# Uni-2_32.net
KiCad netlist of a schematic drawn in EAGLE
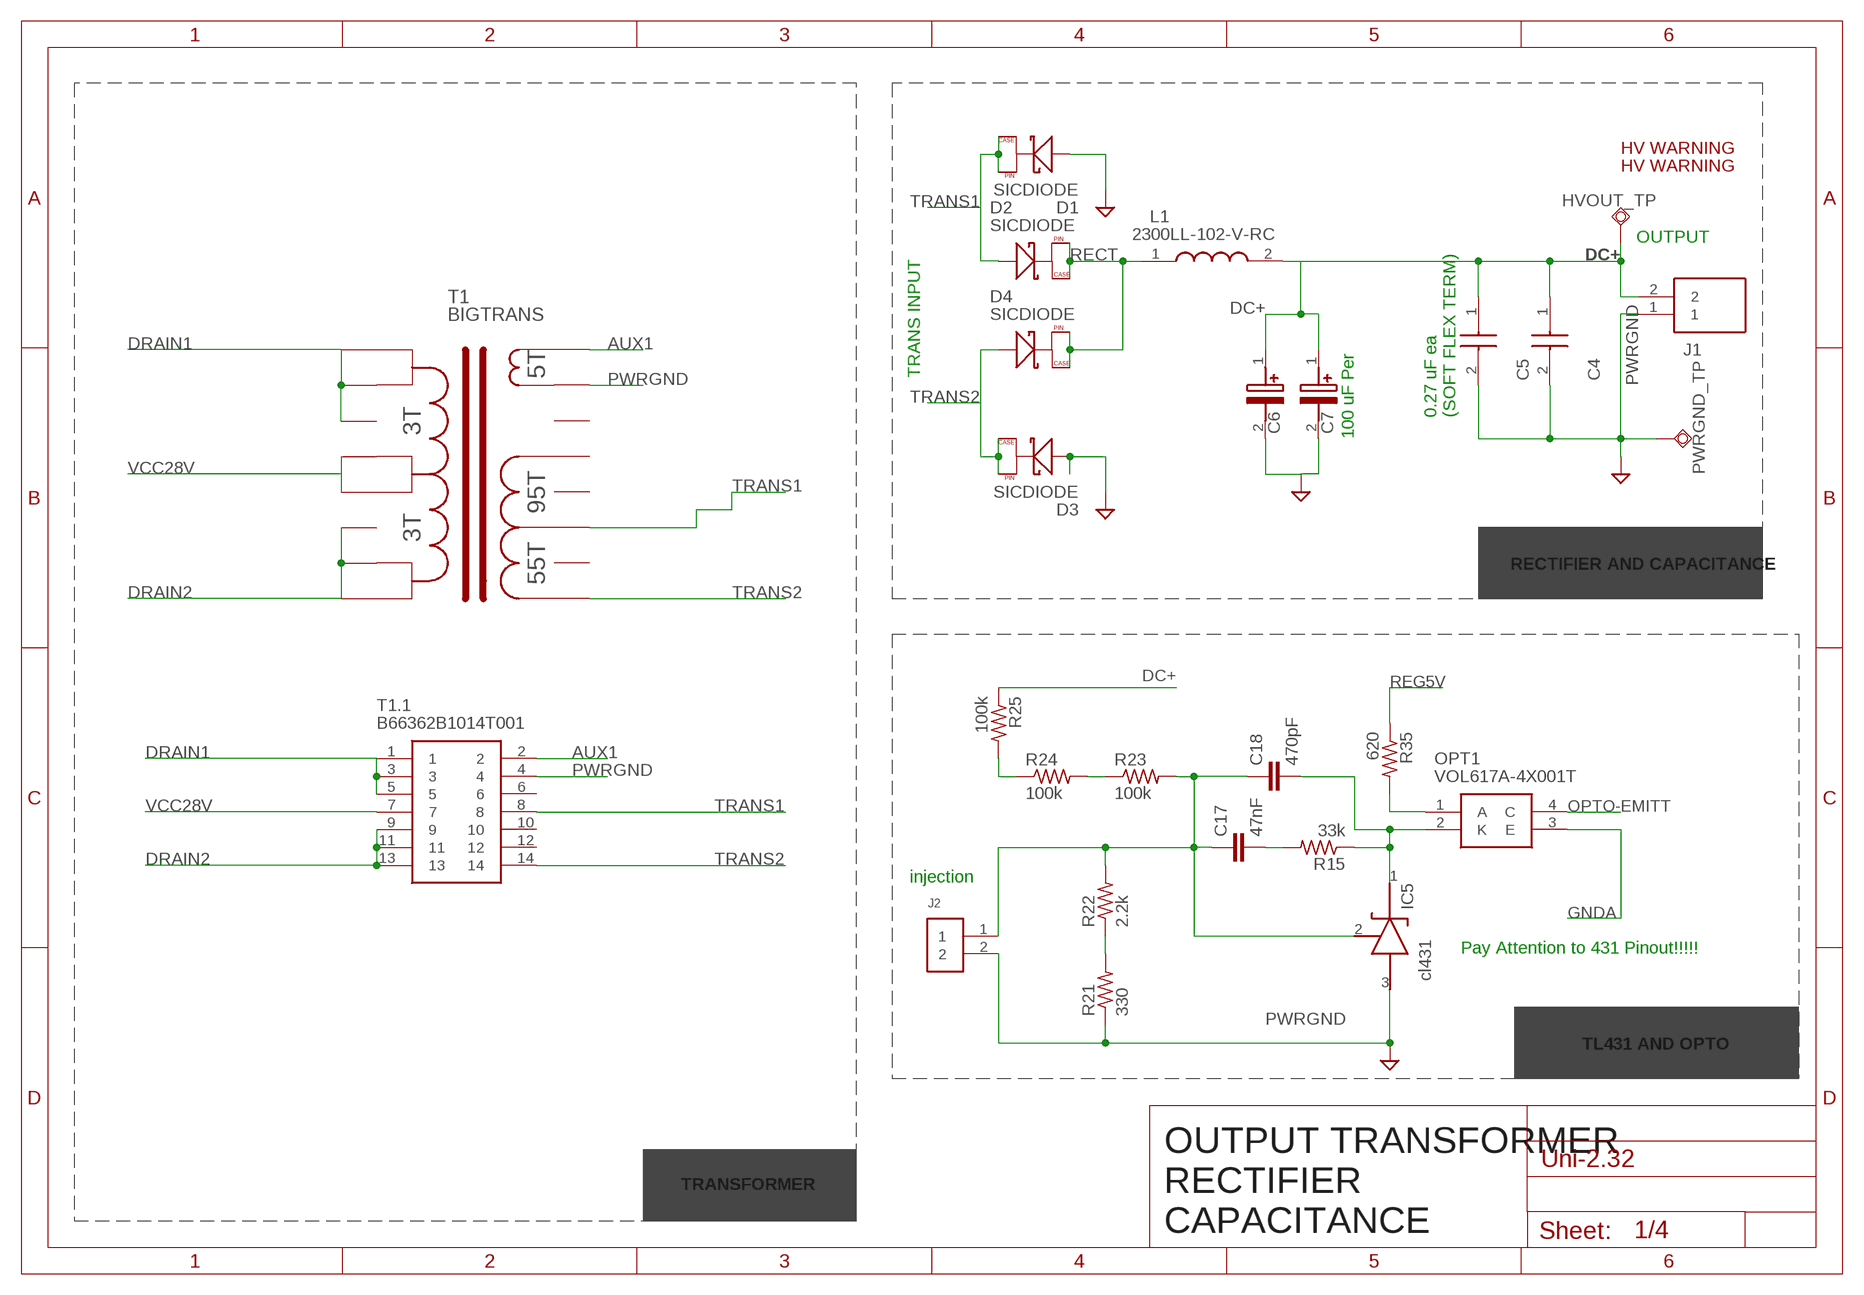
[diagram p0: schematic, sheet 1]
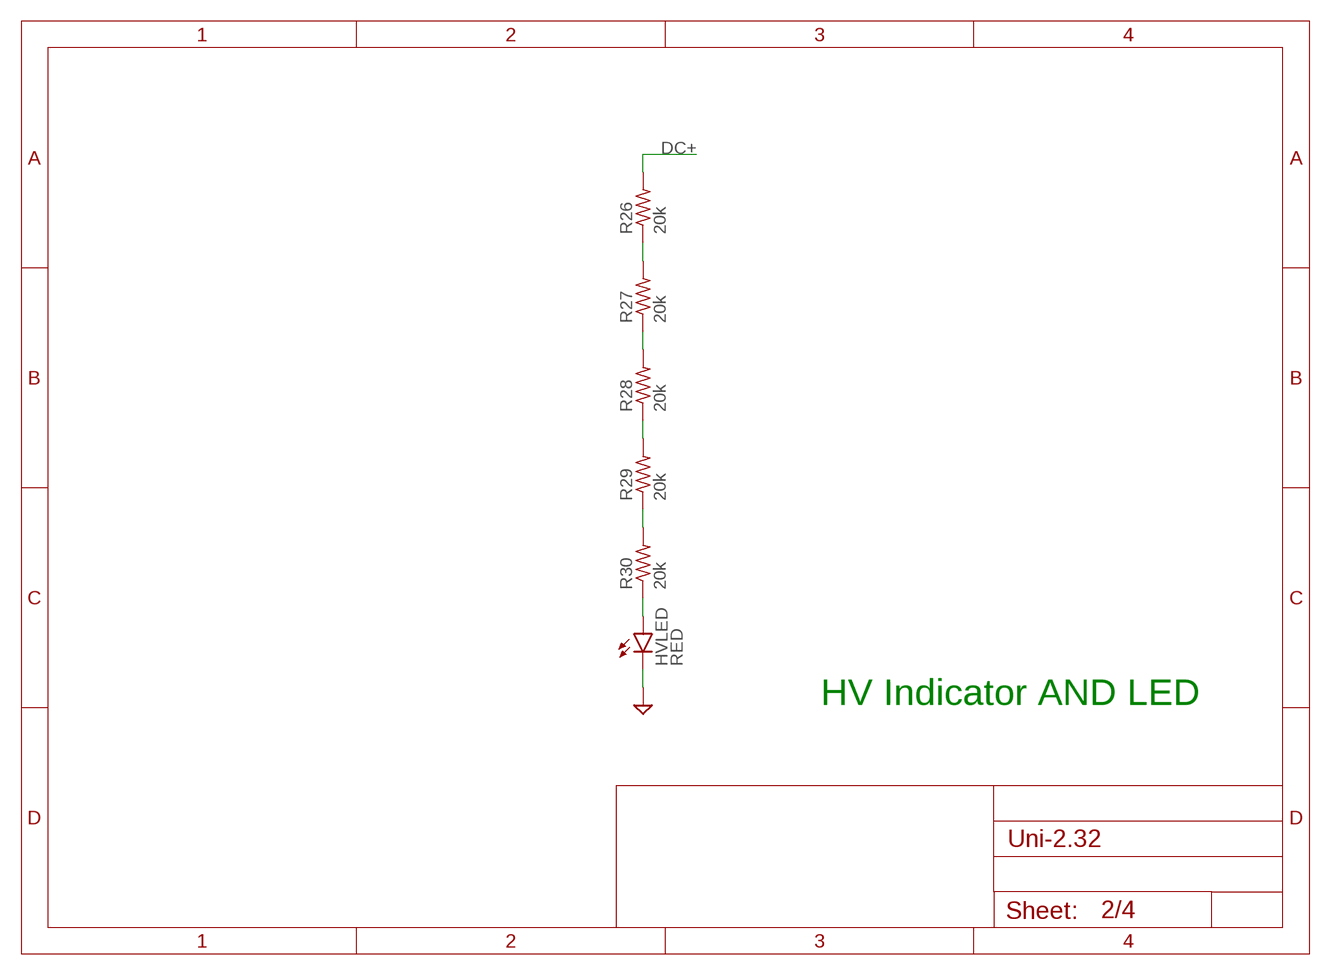
[diagram p1: schematic, sheet 2]
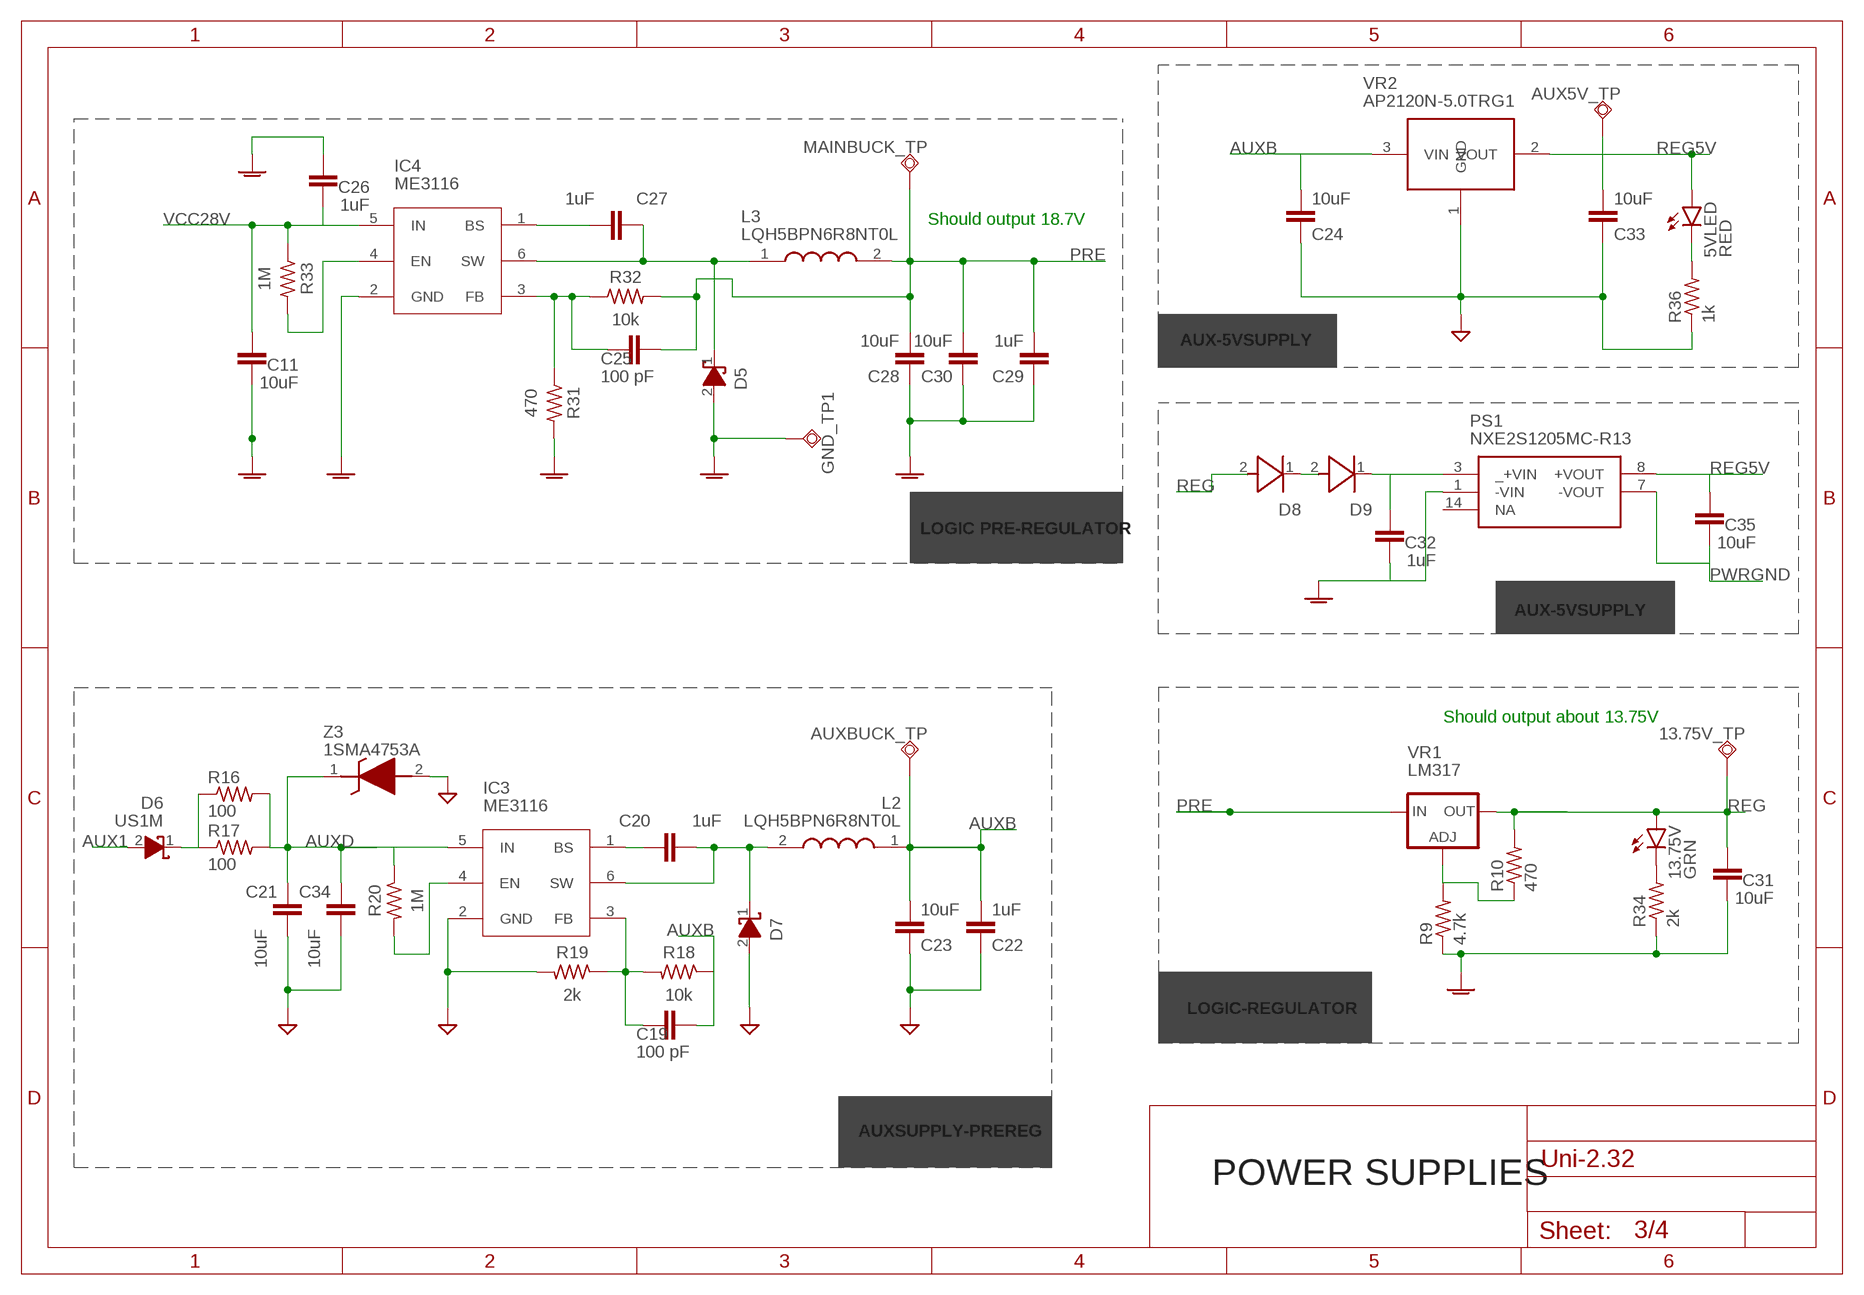
[diagram p2: schematic, sheet 3]
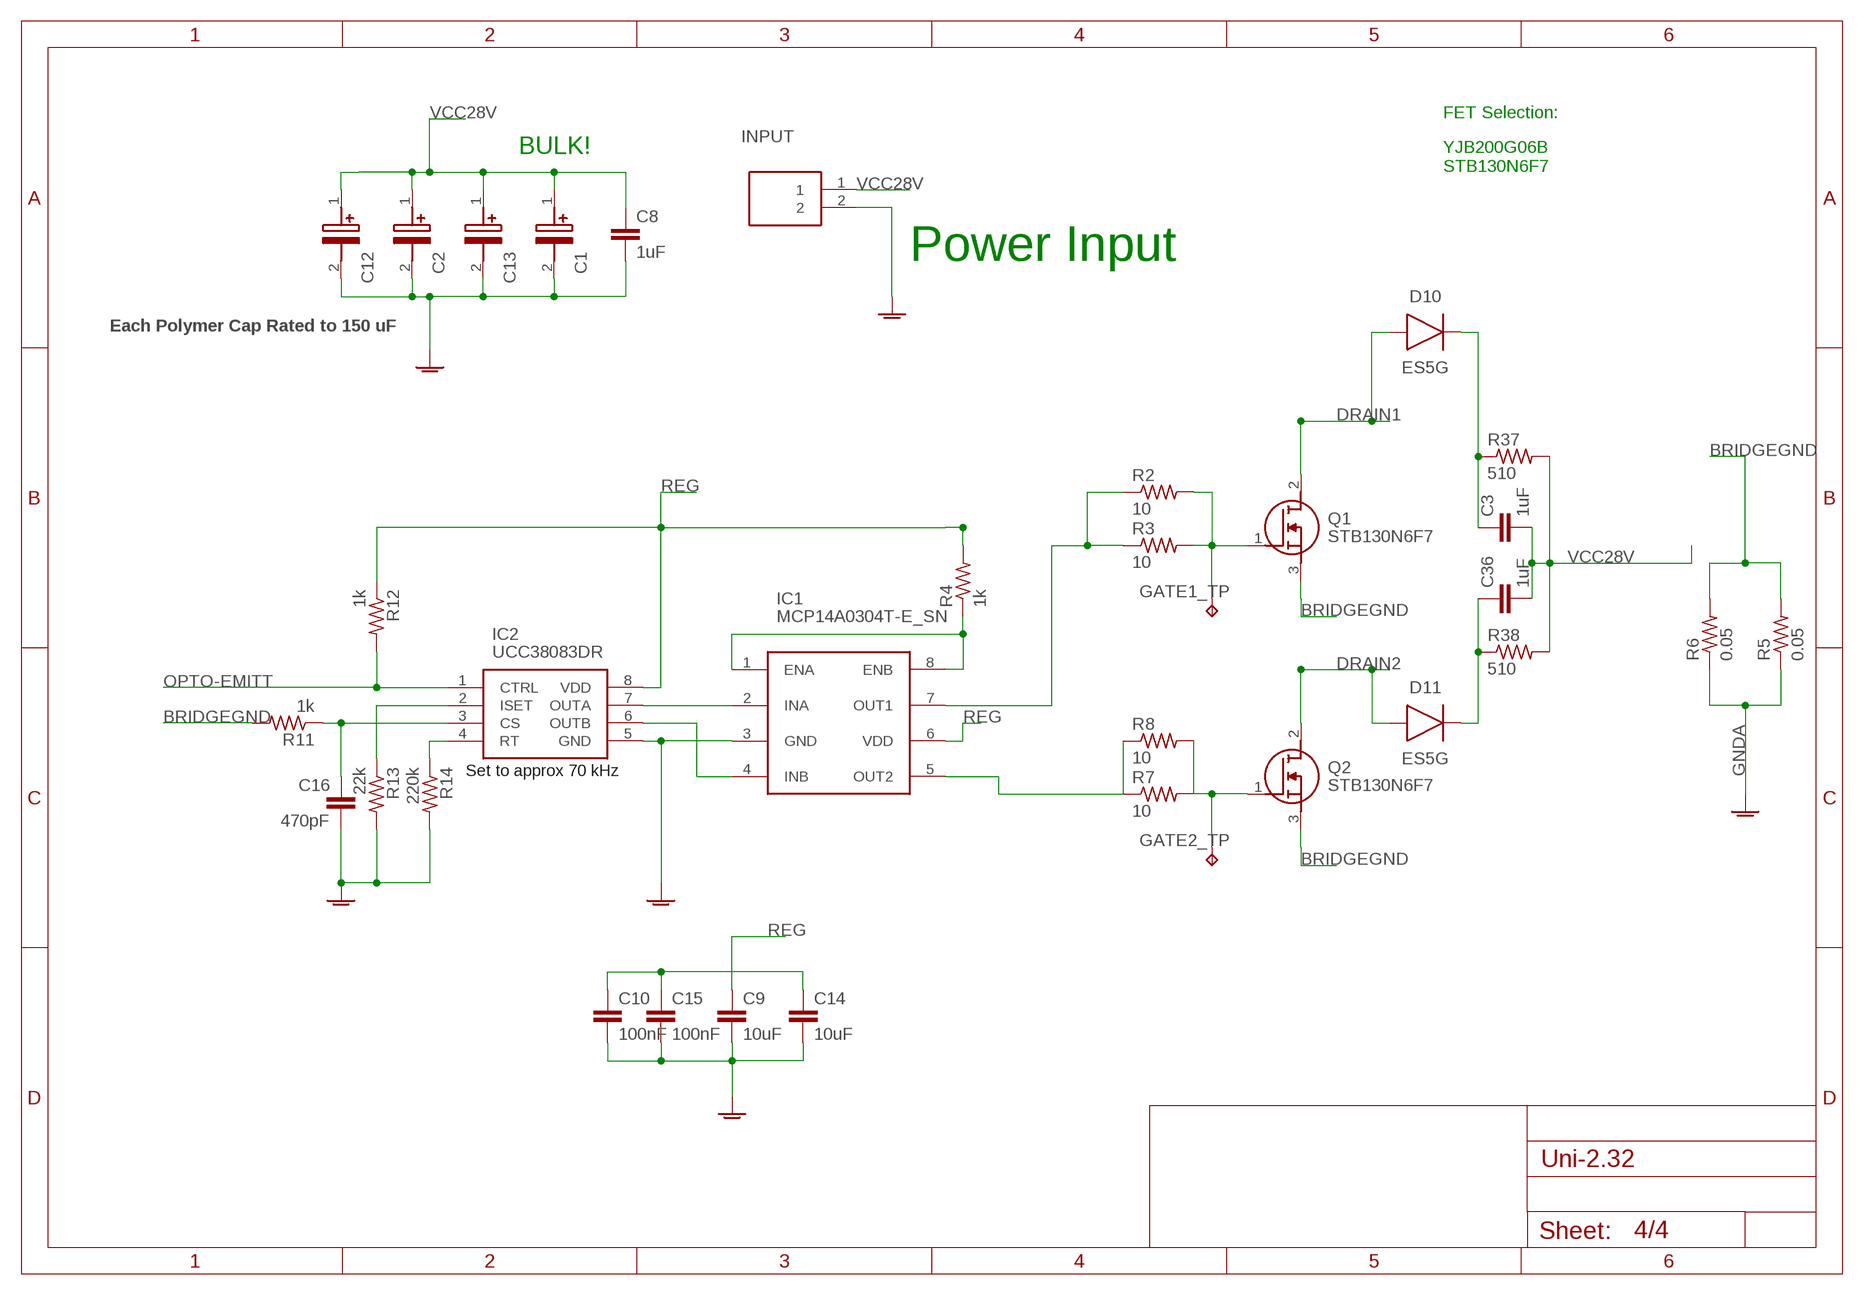
[diagram p3: schematic, sheet 4]

(export (version "E")
  (design (tool "Eeschema 10.0.6"))
  (components
    (comp (ref "C1")
      (value "OVK151M1VTR-10131")
      (footprint "eagle-import:16SVF1000M")
      (libsource (lib "eagle-import") (part "OVK151M1VTR-10131"))
    )
    (comp (ref "C2")
      (value "OVK151M1VTR-10131")
      (footprint "eagle-import:16SVF1000M")
      (libsource (lib "eagle-import") (part "OVK151M1VTR-10131"))
    )
    (comp (ref "C3")
      (value "1uF")
      (footprint "eagle-import:C1206K")
      (libsource (lib "eagle-import") (part "rcl_334_C-EUC1206K"))
    )
    (comp (ref "C8")
      (value "1uF")
      (footprint "eagle-import:C0805K")
      (fields (field (name "LCSC_PART") "C440198"))
      (libsource (lib "eagle-import") (part "rcl_334_C-EUC0805K"))
    )
    (comp (ref "C9")
      (value "10uF")
      (footprint "eagle-import:C0603K")
      (fields (field (name "LCSC_PART") "C440198"))
      (libsource (lib "eagle-import") (part "rcl_334_C-EUC0603K"))
    )
    (comp (ref "C10")
      (value "100nF")
      (footprint "eagle-import:C0402")
      (fields (field (name "LCSC_PART") "C440198"))
      (libsource (lib "eagle-import") (part "rcl_334_C-EUC0402"))
    )
    (comp (ref "C12")
      (value "OVK151M1VTR-10131")
      (footprint "eagle-import:16SVF1000M")
      (libsource (lib "eagle-import") (part "OVK151M1VTR-10131"))
    )
    (comp (ref "C13")
      (value "OVK151M1VTR-10131")
      (footprint "eagle-import:16SVF1000M")
      (libsource (lib "eagle-import") (part "OVK151M1VTR-10131"))
    )
    (comp (ref "C14")
      (value "10uF")
      (footprint "eagle-import:C0603K")
      (fields (field (name "LCSC_PART") "C440198"))
      (libsource (lib "eagle-import") (part "rcl_334_C-EUC0603K"))
    )
    (comp (ref "C15")
      (value "100nF")
      (footprint "eagle-import:C0402")
      (fields (field (name "LCSC_PART") "C440198"))
      (libsource (lib "eagle-import") (part "rcl_334_C-EUC0402"))
    )
    (comp (ref "C16")
      (value "470pF")
      (footprint "eagle-import:C0603K")
      (fields (field (name "LCSC_PART") "C1620"))
      (libsource (lib "eagle-import") (part "rcl_334_C-EUC0603K"))
    )
    (comp (ref "C36")
      (value "1uF")
      (footprint "eagle-import:C1206K")
      (libsource (lib "eagle-import") (part "rcl_334_C-EUC1206K"))
    )
    (comp (ref "D10")
      (value "ES5G")
      (footprint "eagle-import:DIOM5336X265N")
      (fields (field (name "LCSC_PART") "C128705"))
      (libsource (lib "eagle-import") (part "DIODEDO-214AA(SMB)"))
    )
    (comp (ref "D11")
      (value "ES5G")
      (footprint "eagle-import:DIOM5336X265N")
      (libsource (lib "eagle-import") (part "DIODEDO-214AA(SMB)"))
    )
    (comp (ref "GATE1_TP")
      (value "TPTP13R")
      (footprint "eagle-import:TP13R")
      (libsource (lib "eagle-import") (part "TPTP13R"))
    )
    (comp (ref "GATE2_TP")
      (value "TPTP13R")
      (footprint "eagle-import:TP13R")
      (libsource (lib "eagle-import") (part "TPTP13R"))
    )
    (comp (ref "IC1")
      (value "MCP14A0304T-E_SN")
      (footprint "eagle-import:SOIC127P600X175-8N")
      (fields
        (field (name "MANUFACTURER_PART_NUMBER") "MCP14A0304T-E/SN")
        (field (name "MOUSER_PART_NUMBER") "579-MCP14A0304T-E/SN")
      )
      (libsource (lib "eagle-import") (part "MCP14A0304T-E_SN"))
    )
    (comp (ref "IC2")
      (value "UCC38083DR")
      (footprint "eagle-import:SOIC127P600X175-8N")
      (fields (field (name "MOUSER_PART_NUMBER") "595-UCC38083DR"))
      (libsource (lib "eagle-import") (part "UCC38083DR"))
    )
    (comp (ref "INPUT")
      (value "TB005-762-02BE")
      (footprint "eagle-import:TB00576202BE")
      (fields (field (name "MOUSER_PART_NUMBER") "490-TB005-762-02BE"))
      (libsource (lib "eagle-import") (part "TB005-762-02BE"))
    )
    (comp (ref "Q1")
      (value "STB130N6F7")
      (footprint "eagle-import:D2PAK")
      (libsource (lib "eagle-import") (part "STB130N6F7"))
    )
    (comp (ref "Q2")
      (value "STB130N6F7")
      (footprint "eagle-import:D2PAK")
      (libsource (lib "eagle-import") (part "STB130N6F7"))
    )
    (comp (ref "R2")
      (value "10")
      (footprint "eagle-import:R0805")
      (libsource (lib "eagle-import") (part "R-US_R0805"))
    )
    (comp (ref "R3")
      (value "10")
      (footprint "eagle-import:R0805")
      (libsource (lib "eagle-import") (part "R-US_R0805"))
    )
    (comp (ref "R4")
      (value "1k")
      (footprint "eagle-import:R0402")
      (libsource (lib "eagle-import") (part "R-US_R0402"))
    )
    (comp (ref "R5")
      (value "0.05")
      (footprint "eagle-import:R2512")
      (libsource (lib "eagle-import") (part "R-US_R2512"))
    )
    (comp (ref "R6")
      (value "0.05")
      (footprint "eagle-import:R2512")
      (libsource (lib "eagle-import") (part "R-US_R2512"))
    )
    (comp (ref "R7")
      (value "10")
      (footprint "eagle-import:R0805")
      (libsource (lib "eagle-import") (part "R-US_R0805"))
    )
    (comp (ref "R8")
      (value "10")
      (footprint "eagle-import:R0805")
      (libsource (lib "eagle-import") (part "R-US_R0805"))
    )
    (comp (ref "R11")
      (value "1k")
      (footprint "eagle-import:R0603")
      (fields (field (name "LCSC_PART") "C21190"))
      (libsource (lib "eagle-import") (part "R-US_R0603"))
    )
    (comp (ref "R12")
      (value "1k")
      (footprint "eagle-import:R0603")
      (fields (field (name "LCSC_PART") "C22975"))
      (libsource (lib "eagle-import") (part "R-US_R0603"))
    )
    (comp (ref "R13")
      (value "22k")
      (footprint "eagle-import:R0603")
      (fields (field (name "LCSC_PART") "C31850"))
      (libsource (lib "eagle-import") (part "R-US_R0603"))
    )
    (comp (ref "R14")
      (value "220k")
      (footprint "eagle-import:R0603")
      (fields (field (name "LCSC_PART") "C25811"))
      (libsource (lib "eagle-import") (part "R-US_R0603"))
    )
    (comp (ref "R37")
      (value "510")
      (footprint "eagle-import:R2512")
      (libsource (lib "eagle-import") (part "R-US_R2512"))
    )
    (comp (ref "R38")
      (value "510")
      (footprint "eagle-import:R2512")
      (libsource (lib "eagle-import") (part "R-US_R2512"))
    )
    (comp (ref "C4")
      (value "C1812C274KCRACAUTO")
      (footprint "eagle-import:C1812")
      (fields (field (name "MOUSER_PART_NUMBER") "80-C1812C274KCRAUTO"))
      (libsource (lib "eagle-import") (part "C1812C274KCRACAUTO"))
    )
    (comp (ref "C5")
      (value "C1812C274KCRACAUTO")
      (footprint "eagle-import:C1812")
      (fields (field (name "MOUSER_PART_NUMBER") "80-C1812C274KCRAUTO"))
      (libsource (lib "eagle-import") (part "C1812C274KCRACAUTO"))
    )
    (comp (ref "C6")
      (value "400BXW100MEFR18X25")
      (footprint "eagle-import:CAPPRD750W80D1825H2700")
      (libsource (lib "eagle-import") (part "400BXW100MEFR18X25"))
    )
    (comp (ref "C7")
      (value "400BXW100MEFR18X25")
      (footprint "eagle-import:CAPPRD750W80D1825H2700")
      (libsource (lib "eagle-import") (part "400BXW100MEFR18X25"))
    )
    (comp (ref "C17")
      (value "47nF")
      (footprint "eagle-import:C0603K")
      (libsource (lib "eagle-import") (part "rcl_334_C-EUC0603K"))
    )
    (comp (ref "C18")
      (value "470pF")
      (footprint "eagle-import:C0603K")
      (libsource (lib "eagle-import") (part "rcl_334_C-EUC0603K"))
    )
    (comp (ref "D1")
      (value "SICDIODE")
      (footprint "eagle-import:TO-252")
      (libsource (lib "eagle-import") (part "SICDIODE"))
    )
    (comp (ref "D2")
      (value "SICDIODE")
      (footprint "eagle-import:TO-252")
      (libsource (lib "eagle-import") (part "SICDIODE"))
    )
    (comp (ref "D3")
      (value "SICDIODE")
      (footprint "eagle-import:TO-252")
      (libsource (lib "eagle-import") (part "SICDIODE"))
    )
    (comp (ref "D4")
      (value "SICDIODE")
      (footprint "eagle-import:TO-252")
      (libsource (lib "eagle-import") (part "SICDIODE"))
    )
    (comp (ref "HVOUT_TP")
      (value "TPSQPAD1-13")
      (footprint "eagle-import:P1-13")
      (libsource (lib "eagle-import") (part "TPSQPAD1-13"))
    )
    (comp (ref "IC5")
      (value "cl431")
      (footprint "eagle-import:SOT95P237X112-3N")
      (fields
        (field (name "MANUFACTURER_PART_NUMBER") "TL431CL3T")
        (field (name "MOUSER_PART_NUMBER") "511-TL431CL3T")
      )
      (libsource (lib "eagle-import") (part "TL431CL3T"))
    )
    (comp (ref "J1")
      (value "TB005-762-02BE")
      (footprint "eagle-import:TB00576202BE")
      (fields (field (name "MOUSER_PART_NUMBER") "490-TB005-762-02BE"))
      (libsource (lib "eagle-import") (part "TB005-762-02BE"))
    )
    (comp (ref "J2")
      (value "61300211121")
      (footprint "eagle-import:61300211121")
      (fields
        (field (name "DIGI_KEY_PART_NUMBER") "732-5315-ND")
        (field (name "MANUFACTURER") "Wurth Electronics Inc.")
        (field (name "CREATED_BY") "PCBLayout.com")
      )
      (libsource (lib "eagle-import") (part "61300211121"))
    )
    (comp (ref "L1")
      (value "2300LL-102-V-RC")
      (footprint "eagle-import:2300LL102VRC")
      (fields (field (name "MOUSER_PART_NUMBER") "652-2300LL-102-V-RC"))
      (libsource (lib "eagle-import") (part "2300LL-102-V-RC"))
    )
    (comp (ref "OPT1")
      (value "VOL617A-4X001T")
      (footprint "eagle-import:SOP254P1015X230-4N")
      (fields (field (name "MOUSER_PART_NUMBER") "78-VOL617A-4X001T"))
      (libsource (lib "eagle-import") (part "VOL617A-4X001T"))
    )
    (comp (ref "PWRGND_TP")
      (value "TPSQPAD1-13")
      (footprint "eagle-import:P1-13")
      (libsource (lib "eagle-import") (part "TPSQPAD1-13"))
    )
    (comp (ref "R15")
      (value "33k")
      (footprint "eagle-import:R0603")
      (libsource (lib "eagle-import") (part "R-US_R0603"))
    )
    (comp (ref "R21")
      (value "330")
      (footprint "eagle-import:R0805")
      (libsource (lib "eagle-import") (part "R-US_R0805"))
    )
    (comp (ref "R22")
      (value "2.2k")
      (footprint "eagle-import:R0805")
      (libsource (lib "eagle-import") (part "R-US_R0805"))
    )
    (comp (ref "R23")
      (value "100k")
      (footprint "eagle-import:R1206")
      (libsource (lib "eagle-import") (part "R-US_R1206"))
    )
    (comp (ref "R24")
      (value "100k")
      (footprint "eagle-import:R1206")
      (libsource (lib "eagle-import") (part "R-US_R1206"))
    )
    (comp (ref "R25")
      (value "100k")
      (footprint "eagle-import:R1206")
      (libsource (lib "eagle-import") (part "R-US_R1206"))
    )
    (comp (ref "R35")
      (value "620")
      (footprint "eagle-import:R0603")
      (libsource (lib "eagle-import") (part "R-US_R0603"))
    )
    (comp (ref "T1")
      (value "BIGTRANS")
      (footprint "eagle-import:BIGTRANS!")
      (libsource (lib "eagle-import") (part "BIGTRANS"))
    )
    (comp (ref "T1.1")
      (value "B66362B1014T001")
      (footprint "eagle-import:B66362B1014T001")
      (fields (field (name "MOUSER_PART_NUMBER") "871-B66362B1014T001"))
      (libsource (lib "eagle-import") (part "B66362B1014T001"))
    )
    (comp (ref "U$3")
      (value "HV")
      (footprint "eagle-import:PSFBC_ELECTRIC_SHOCK")
      (libsource (lib "eagle-import") (part "HV"))
    )
    (comp (ref "U$4")
      (value "HV")
      (footprint "eagle-import:PSFBC_ELECTRIC_SHOCK")
      (libsource (lib "eagle-import") (part "HV"))
    )
    (comp (ref "HVLED")
      (value "RED")
      (footprint "eagle-import:CHIPLED_0805")
      (libsource (lib "eagle-import") (part "LEDCHIPLED_0805"))
    )
    (comp (ref "R26")
      (value "20k")
      (footprint "eagle-import:R1206")
      (libsource (lib "eagle-import") (part "R-US_R1206"))
    )
    (comp (ref "R27")
      (value "20k")
      (footprint "eagle-import:R1206")
      (libsource (lib "eagle-import") (part "R-US_R1206"))
    )
    (comp (ref "R28")
      (value "20k")
      (footprint "eagle-import:R1206")
      (libsource (lib "eagle-import") (part "R-US_R1206"))
    )
    (comp (ref "R29")
      (value "20k")
      (footprint "eagle-import:R1206")
      (libsource (lib "eagle-import") (part "R-US_R1206"))
    )
    (comp (ref "R30")
      (value "20k")
      (footprint "eagle-import:R1206")
      (libsource (lib "eagle-import") (part "R-US_R1206"))
    )
    (comp (ref "5VLED")
      (value "RED")
      (footprint "eagle-import:CHIPLED_0805")
      (fields (field (name "LCSC_PART") "C72043"))
      (libsource (lib "eagle-import") (part "LEDCHIPLED_0805"))
    )
    (comp (ref "13.75V")
      (value "GRN")
      (footprint "eagle-import:CHIPLED_0805")
      (fields (field (name "LCSC_PART") "C72043"))
      (libsource (lib "eagle-import") (part "LEDCHIPLED_0805"))
    )
    (comp (ref "13.75V_TP")
      (value "TPSQPAD1-17")
      (footprint "eagle-import:P1-17")
      (libsource (lib "eagle-import") (part "TPSQPAD1-17"))
    )
    (comp (ref "AUX5V_TP")
      (value "TPSQPAD1-17")
      (footprint "eagle-import:P1-17")
      (libsource (lib "eagle-import") (part "TPSQPAD1-17"))
    )
    (comp (ref "AUXBUCK_TP")
      (value "TPSQPAD1-17")
      (footprint "eagle-import:P1-17")
      (libsource (lib "eagle-import") (part "TPSQPAD1-17"))
    )
    (comp (ref "C11")
      (value "10uF")
      (footprint "eagle-import:C0805K")
      (fields (field (name "LCSC_PART") "C440198"))
      (libsource (lib "eagle-import") (part "C-EUC0805K"))
    )
    (comp (ref "C19")
      (value "100 pF")
      (footprint "eagle-import:C0402K")
      (fields (field (name "LCSC_PART") "C1546"))
      (libsource (lib "eagle-import") (part "rcl_334_C-EUC0402K"))
    )
    (comp (ref "C20")
      (value "1uF")
      (footprint "eagle-import:C0603K")
      (fields (field (name "LCSC_PART") "C14663"))
      (libsource (lib "eagle-import") (part "rcl_334_C-EUC0603K"))
    )
    (comp (ref "C21")
      (value "10uF")
      (footprint "eagle-import:C0805K")
      (libsource (lib "eagle-import") (part "rcl_334_C-EUC0805K"))
    )
    (comp (ref "C22")
      (value "1uF")
      (footprint "eagle-import:C0402")
      (fields (field (name "LCSC_PART") "C440198"))
      (libsource (lib "eagle-import") (part "rcl_334_C-EUC0402"))
    )
    (comp (ref "C23")
      (value "10uF")
      (footprint "eagle-import:C0603K")
      (fields (field (name "LCSC_PART") "C440198"))
      (libsource (lib "eagle-import") (part "rcl_334_C-EUC0603K"))
    )
    (comp (ref "C24")
      (value "10uF")
      (footprint "eagle-import:C0603K")
      (fields (field (name "LCSC_PART") "C440198"))
      (libsource (lib "eagle-import") (part "rcl_334_C-EUC0603K"))
    )
    (comp (ref "C25")
      (value "100 pF")
      (footprint "eagle-import:C0402K")
      (fields (field (name "LCSC_PART") "C1546"))
      (libsource (lib "eagle-import") (part "rcl_334_C-EUC0402K"))
    )
    (comp (ref "C26")
      (value "1uF")
      (footprint "eagle-import:C0603K")
      (fields (field (name "LCSC_PART") "C440198"))
      (libsource (lib "eagle-import") (part "rcl_334_C-EUC0603K"))
    )
    (comp (ref "C27")
      (value "1uF")
      (footprint "eagle-import:C0603K")
      (fields (field (name "LCSC_PART") "C14663"))
      (libsource (lib "eagle-import") (part "rcl_334_C-EUC0603K"))
    )
    (comp (ref "C28")
      (value "10uF")
      (footprint "eagle-import:C0603K")
      (fields (field (name "LCSC_PART") "C440198"))
      (libsource (lib "eagle-import") (part "C-EUC0603K"))
    )
    (comp (ref "C29")
      (value "1uF")
      (footprint "eagle-import:C0603K")
      (fields (field (name "LCSC_PART") "C440198"))
      (libsource (lib "eagle-import") (part "C-EUC0603K"))
    )
    (comp (ref "C30")
      (value "10uF")
      (footprint "eagle-import:C0603K")
      (fields (field (name "LCSC_PART") "C440198"))
      (libsource (lib "eagle-import") (part "C-EUC0603K"))
    )
    (comp (ref "C31")
      (value "10uF")
      (footprint "eagle-import:C0603K")
      (fields (field (name "LCSC_PART") "C440198"))
      (libsource (lib "eagle-import") (part "C-EUC0603K"))
    )
    (comp (ref "C32")
      (value "1uF")
      (footprint "eagle-import:C0603K")
      (fields (field (name "LCSC_PART") "C440198"))
      (libsource (lib "eagle-import") (part "rcl_334_C-EUC0603K"))
    )
    (comp (ref "C33")
      (value "10uF")
      (footprint "eagle-import:C0603K")
      (libsource (lib "eagle-import") (part "rcl_334_C-EUC0603K"))
    )
    (comp (ref "C34")
      (value "10uF")
      (footprint "eagle-import:C0805K")
      (libsource (lib "eagle-import") (part "rcl_334_C-EUC0805K"))
    )
    (comp (ref "C35")
      (value "10uF")
      (footprint "eagle-import:C0603K")
      (fields (field (name "LCSC_PART") "C440198"))
      (libsource (lib "eagle-import") (part "rcl_334_C-EUC0603K"))
    )
    (comp (ref "D5")
      (value "SCHOTTKY")
      (footprint "eagle-import:DIOM5127X229N")
      (fields
        (field (name "MANUFACTURER_PART_NUMBER") "SS16HE3_B/H")
        (field (name "MOUSER_PART_NUMBER") "78-SS16HE3_B/H")
        (field (name "LCSC_PART") "C22452")
      )
      (libsource (lib "eagle-import") (part "SCHOTTKY"))
    )
    (comp (ref "D6")
      (value "US1M")
      (footprint "eagle-import:DIOM5127X229N")
      (fields
        (field (name "MANUFACTURER_PART_NUMBER") "SS16HE3_B/H")
        (field (name "MOUSER_PART_NUMBER") "78-SS16HE3_B/H")
      )
      (libsource (lib "eagle-import") (part "SCHOTTKY"))
    )
    (comp (ref "D7")
      (value "SCHOTTKY")
      (footprint "eagle-import:DIOM5127X229N")
      (fields
        (field (name "MANUFACTURER_PART_NUMBER") "SS16HE3_B/H")
        (field (name "MOUSER_PART_NUMBER") "78-SS16HE3_B/H")
        (field (name "LCSC_PART") "C22452")
      )
      (libsource (lib "eagle-import") (part "SCHOTTKY"))
    )
    (comp (ref "D8")
      (value "SM4007PL")
      (footprint "eagle-import:SOD3716X145N")
      (fields
        (field (name "MANUFACTURER_PART_NUMBER") "1N4148W-7-F")
        (field (name "MOUSER_PART_NUMBER") "621-1N4148W-F")
        (field (name "LCSC_PART") "C64898")
      )
      (libsource (lib "eagle-import") (part "1N4148W-7-F"))
    )
    (comp (ref "D9")
      (value "SM4007PL")
      (footprint "eagle-import:SOD3716X145N")
      (fields
        (field (name "MANUFACTURER_PART_NUMBER") "1N4148W-7-F")
        (field (name "MOUSER_PART_NUMBER") "621-1N4148W-F")
        (field (name "LCSC_PART") "C64898")
      )
      (libsource (lib "eagle-import") (part "1N4148W-7-F"))
    )
    (comp (ref "GND_TP1")
      (value "TPSQPAD1-13")
      (footprint "eagle-import:P1-13")
      (libsource (lib "eagle-import") (part "TPSQPAD1-13"))
    )
    (comp (ref "IC3")
      (value "ME3116")
      (footprint "eagle-import:SOT95P280X100-6N")
      (fields (field (name "LCSC_PART") "C97643"))
      (libsource (lib "eagle-import") (part "ME3116"))
    )
    (comp (ref "IC4")
      (value "ME3116")
      (footprint "eagle-import:SOT95P280X100-6N")
      (fields (field (name "LCSC_PART") "C97643"))
      (libsource (lib "eagle-import") (part "ME3116"))
    )
    (comp (ref "L2")
      (value "LQH5BPN6R8NT0L")
      (footprint "eagle-import:LQH5BPB100MT0L")
      (fields (field (name "MOUSER_PART_NUMBER") "81-LQH5BPN6R8NT0L0L"))
      (libsource (lib "eagle-import") (part "LQH5BPN6R8NT0L"))
    )
    (comp (ref "L3")
      (value "LQH5BPN6R8NT0L")
      (footprint "eagle-import:LQH5BPB100MT0L")
      (fields (field (name "MOUSER_PART_NUMBER") "81-LQH5BPN6R8NT0L0L"))
      (libsource (lib "eagle-import") (part "LQH5BPN6R8NT0L"))
    )
    (comp (ref "MAINBUCK_TP")
      (value "TPSQPAD1-17")
      (footprint "eagle-import:P1-17")
      (libsource (lib "eagle-import") (part "TPSQPAD1-17"))
    )
    (comp (ref "PS1")
      (value "NXE2S1205MC-R13")
      (footprint "eagle-import:NXE2S1205MCR13")
      (fields (field (name "MOUSER_PART_NUMBER") "580-NXE2S1205MC-R13"))
      (libsource (lib "eagle-import") (part "NXE2S1205MC-R13"))
    )
    (comp (ref "R9")
      (value "4.7k")
      (footprint "eagle-import:R0603")
      (fields (field (name "LCSC_PART") "C22975"))
      (libsource (lib "eagle-import") (part "R-US_R0603"))
    )
    (comp (ref "R10")
      (value "470")
      (footprint "eagle-import:R0603")
      (fields (field (name "LCSC_PART") "C22975"))
      (libsource (lib "eagle-import") (part "R-US_R0603"))
    )
    (comp (ref "R16")
      (value "100")
      (footprint "eagle-import:R1206")
      (libsource (lib "eagle-import") (part "R-US_R1206"))
    )
    (comp (ref "R17")
      (value "100")
      (footprint "eagle-import:R1206")
      (libsource (lib "eagle-import") (part "R-US_R1206"))
    )
    (comp (ref "R18")
      (value "10k")
      (footprint "eagle-import:R0402")
      (fields (field (name "LCSC_PART") "C25779"))
      (libsource (lib "eagle-import") (part "R-US_R0402"))
    )
    (comp (ref "R19")
      (value "2k")
      (footprint "eagle-import:R0402")
      (fields (field (name "LCSC_PART") "C25779"))
      (libsource (lib "eagle-import") (part "R-US_R0402"))
    )
    (comp (ref "R20")
      (value "1M")
      (footprint "eagle-import:R0402")
      (fields (field (name "LCSC_PART") "C25741") (field (name "SPICEPREFIX") "R"))
      (libsource (lib "eagle-import") (part "R-US_R0402"))
    )
    (comp (ref "R31")
      (value "470")
      (footprint "eagle-import:R0603")
      (fields (field (name "LCSC_PART") "C4177") (field (name "SPICEPREFIX") "R"))
      (libsource (lib "eagle-import") (part "R-US_R0603"))
    )
    (comp (ref "R32")
      (value "10k")
      (footprint "eagle-import:R0402")
      (fields (field (name "LCSC_PART") "C25779"))
      (libsource (lib "eagle-import") (part "R-US_R0402"))
    )
    (comp (ref "R33")
      (value "1M")
      (footprint "eagle-import:R0402")
      (fields (field (name "LCSC_PART") "C25741") (field (name "SPICEPREFIX") "R"))
      (libsource (lib "eagle-import") (part "R-US_R0402"))
    )
    (comp (ref "R34")
      (value "2k")
      (footprint "eagle-import:R0603")
      (fields (field (name "LCSC_PART") "C22975"))
      (libsource (lib "eagle-import") (part "R-US_R0603"))
    )
    (comp (ref "R36")
      (value "1k")
      (footprint "eagle-import:R0603")
      (fields (field (name "LCSC_PART") "C22975"))
      (libsource (lib "eagle-import") (part "R-US_R0603"))
    )
    (comp (ref "VR1")
      (value "LM317")
      (footprint "eagle-import:DPACK")
      (libsource (lib "eagle-import") (part "LM317?MBDT"))
    )
    (comp (ref "VR2")
      (value "AP2120N-5.0TRG1")
      (footprint "eagle-import:SOT95P240X120-3N")
      (fields (field (name "MOUSER_PART_NUMBER") "621-AP2120N-5.0TRG1"))
      (libsource (lib "eagle-import") (part "AP2120N-5.0TRG1"))
    )
    (comp (ref "Z3")
      (value "1SMA4753A")
      (footprint "eagle-import:DIOM5226X220N")
      (fields
        (field (name "MANUFACTURER_PART_NUMBER") "1SMA5942BT3G")
        (field (name "MOUSER_PART_NUMBER") "863-1SMA5942BT3G")
        (field (name "LCSC_PART") "C362284")
      )
      (libsource (lib "eagle-import") (part "1SMA5942BT3G"))
    )
  )
  (nets
    (net (code "1") (name "AUX1") (class "Default")
      (node (ref "D6") (pin "2") (pinfunction "A_2") (pintype "bidirectional"))
      (node (ref "T1") (pin "16") (pinfunction "16_16") (pintype "bidirectional"))
      (node (ref "T1.1") (pin "2") (pinfunction "2_2") (pintype "bidirectional"))
    )
    (net (code "2") (name "AUXB") (class "Default")
      (node (ref "AUXBUCK_TP") (pin "TP") (pinfunction "TP_TP") (pintype "input"))
      (node (ref "C19") (pin "1") (pinfunction "1_1") (pintype "passive"))
      (node (ref "C22") (pin "2") (pinfunction "2_2") (pintype "passive"))
      (node (ref "C23") (pin "2") (pinfunction "2_2") (pintype "passive"))
      (node (ref "C24") (pin "2") (pinfunction "2_2") (pintype "passive"))
      (node (ref "L2") (pin "1") (pinfunction "1_1") (pintype "bidirectional"))
      (node (ref "R18") (pin "1") (pinfunction "1_1") (pintype "passive"))
      (node (ref "VR2") (pin "3") (pinfunction "VIN_3") (pintype "bidirectional"))
    )
    (net (code "3") (name "AUXD") (class "Default")
      (node (ref "C21") (pin "1") (pinfunction "1_1") (pintype "passive"))
      (node (ref "C34") (pin "1") (pinfunction "1_1") (pintype "passive"))
      (node (ref "IC3") (pin "5") (pinfunction "IN_5") (pintype "bidirectional"))
      (node (ref "R16") (pin "2") (pinfunction "2_2") (pintype "passive"))
      (node (ref "R17") (pin "2") (pinfunction "2_2") (pintype "passive"))
      (node (ref "R20") (pin "1") (pinfunction "1_1") (pintype "passive"))
      (node (ref "Z3") (pin "1") (pinfunction "K_1") (pintype "bidirectional"))
    )
    (net (code "4") (name "BRIDGEGND") (class "Default")
      (node (ref "Q1") (pin "3") (pinfunction "S_3") (pintype "bidirectional"))
      (node (ref "Q2") (pin "3") (pinfunction "S_3") (pintype "bidirectional"))
      (node (ref "R11") (pin "2") (pinfunction "2_2") (pintype "passive"))
      (node (ref "R5") (pin "2") (pinfunction "2_2") (pintype "passive"))
      (node (ref "R6") (pin "2") (pinfunction "2_2") (pintype "passive"))
    )
    (net (code "5") (name "DC+") (class "Default")
      (node (ref "C4") (pin "1") (pinfunction "1_1") (pintype "bidirectional"))
      (node (ref "C5") (pin "1") (pinfunction "1_1") (pintype "bidirectional"))
      (node (ref "C6") (pin "1") (pinfunction "+_1") (pintype "bidirectional"))
      (node (ref "C7") (pin "1") (pinfunction "+_1") (pintype "bidirectional"))
      (node (ref "HVOUT_TP") (pin "TP") (pinfunction "TP_TP") (pintype "input"))
      (node (ref "J1") (pin "2") (pinfunction "2_2") (pintype "bidirectional"))
      (node (ref "L1") (pin "2") (pinfunction "2_2") (pintype "bidirectional"))
      (node (ref "R25") (pin "1") (pinfunction "1_1") (pintype "passive"))
      (node (ref "R26") (pin "2") (pinfunction "2_2") (pintype "passive"))
    )
    (net (code "6") (name "DRAIN1") (class "Default")
      (node (ref "D10") (pin "2") (pinfunction "A_2") (pintype "passive"))
      (node (ref "Q1") (pin "2") (pinfunction "D_2") (pintype "bidirectional"))
      (node (ref "T1") (pin "6") (pinfunction "6_6") (pintype "bidirectional"))
      (node (ref "T1") (pin "7") (pinfunction "7_7") (pintype "bidirectional"))
      (node (ref "T1") (pin "8") (pinfunction "8_8") (pintype "bidirectional"))
      (node (ref "T1.1") (pin "1") (pinfunction "1_1") (pintype "bidirectional"))
      (node (ref "T1.1") (pin "3") (pinfunction "3_3") (pintype "bidirectional"))
      (node (ref "T1.1") (pin "5") (pinfunction "5_5") (pintype "bidirectional"))
    )
    (net (code "7") (name "DRAIN2") (class "Default")
      (node (ref "D11") (pin "2") (pinfunction "A_2") (pintype "passive"))
      (node (ref "Q2") (pin "2") (pinfunction "D_2") (pintype "bidirectional"))
      (node (ref "T1") (pin "1") (pinfunction "1_1") (pintype "bidirectional"))
      (node (ref "T1") (pin "2") (pinfunction "2_2") (pintype "bidirectional"))
      (node (ref "T1") (pin "3") (pinfunction "3_3") (pintype "bidirectional"))
      (node (ref "T1.1") (pin "11") (pinfunction "11_11") (pintype "bidirectional"))
      (node (ref "T1.1") (pin "13") (pinfunction "13_13") (pintype "bidirectional"))
      (node (ref "T1.1") (pin "9") (pinfunction "9_9") (pintype "bidirectional"))
    )
    (net (code "8") (name "GNDA") (class "Default")
      (node (ref "C1") (pin "2") (pinfunction "-_2") (pintype "bidirectional"))
      (node (ref "C10") (pin "2") (pinfunction "2_2") (pintype "passive"))
      (node (ref "C11") (pin "1") (pinfunction "1_1") (pintype "passive"))
      (node (ref "C12") (pin "2") (pinfunction "-_2") (pintype "bidirectional"))
      (node (ref "C13") (pin "2") (pinfunction "-_2") (pintype "bidirectional"))
      (node (ref "C14") (pin "2") (pinfunction "2_2") (pintype "passive"))
      (node (ref "C15") (pin "2") (pinfunction "2_2") (pintype "passive"))
      (node (ref "C16") (pin "2") (pinfunction "2_2") (pintype "passive"))
      (node (ref "C2") (pin "2") (pinfunction "-_2") (pintype "bidirectional"))
      (node (ref "C26") (pin "2") (pinfunction "2_2") (pintype "passive"))
      (node (ref "C28") (pin "1") (pinfunction "1_1") (pintype "passive"))
      (node (ref "C29") (pin "1") (pinfunction "1_1") (pintype "passive"))
      (node (ref "C30") (pin "1") (pinfunction "1_1") (pintype "passive"))
      (node (ref "C31") (pin "1") (pinfunction "1_1") (pintype "passive"))
      (node (ref "C32") (pin "1") (pinfunction "1_1") (pintype "passive"))
      (node (ref "C8") (pin "2") (pinfunction "2_2") (pintype "passive"))
      (node (ref "C9") (pin "2") (pinfunction "2_2") (pintype "passive"))
      (node (ref "D5") (pin "2") (pinfunction "A_2") (pintype "bidirectional"))
      (node (ref "GND_TP1") (pin "TP") (pinfunction "TP_TP") (pintype "input"))
      (node (ref "IC1") (pin "3") (pinfunction "GND_3") (pintype "bidirectional"))
      (node (ref "IC2") (pin "5") (pinfunction "GND_5") (pintype "bidirectional"))
      (node (ref "IC4") (pin "2") (pinfunction "GND_2") (pintype "bidirectional"))
      (node (ref "INPUT") (pin "2") (pinfunction "2_2") (pintype "bidirectional"))
      (node (ref "OPT1") (pin "3") (pinfunction "E_3") (pintype "bidirectional"))
      (node (ref "PS1") (pin "1") (pinfunction "-VIN_1") (pintype "bidirectional"))
      (node (ref "R13") (pin "2") (pinfunction "2_2") (pintype "passive"))
      (node (ref "R14") (pin "2") (pinfunction "2_2") (pintype "passive"))
      (node (ref "R31") (pin "2") (pinfunction "2_2") (pintype "passive"))
      (node (ref "R34") (pin "1") (pinfunction "1_1") (pintype "passive"))
      (node (ref "R5") (pin "1") (pinfunction "1_1") (pintype "passive"))
      (node (ref "R6") (pin "1") (pinfunction "1_1") (pintype "passive"))
      (node (ref "R9") (pin "1") (pinfunction "1_1") (pintype "passive"))
    )
    (net (code "9") (name "Net-(5VLED-PadC)") (class "Default")
      (node (ref "5VLED") (pin "C") (pinfunction "C_C") (pintype "passive"))
      (node (ref "R36") (pin "2") (pinfunction "2_2") (pintype "passive"))
    )
    (net (code "10") (name "Net-(13.75V-PadC)") (class "Default")
      (node (ref "13.75V") (pin "C") (pinfunction "C_C") (pintype "passive"))
      (node (ref "R34") (pin "2") (pinfunction "2_2") (pintype "passive"))
    )
    (net (code "11") (name "Net-(C17-Pad2)") (class "Default")
      (node (ref "C17") (pin "2") (pinfunction "2_2") (pintype "passive"))
      (node (ref "R15") (pin "2") (pinfunction "2_2") (pintype "passive"))
    )
    (net (code "12") (name "Net-(D5-K)") (class "Default")
      (node (ref "C27") (pin "1") (pinfunction "1_1") (pintype "passive"))
      (node (ref "D5") (pin "1") (pinfunction "K_1") (pintype "bidirectional"))
      (node (ref "IC4") (pin "6") (pinfunction "SW_6") (pintype "bidirectional"))
      (node (ref "L3") (pin "1") (pinfunction "1_1") (pintype "bidirectional"))
    )
    (net (code "13") (name "Net-(D6-K)") (class "Default")
      (node (ref "D6") (pin "1") (pinfunction "K_1") (pintype "bidirectional"))
      (node (ref "R16") (pin "1") (pinfunction "1_1") (pintype "passive"))
      (node (ref "R17") (pin "1") (pinfunction "1_1") (pintype "passive"))
    )
    (net (code "14") (name "Net-(D7-K)") (class "Default")
      (node (ref "C20") (pin "2") (pinfunction "2_2") (pintype "passive"))
      (node (ref "D7") (pin "1") (pinfunction "K_1") (pintype "bidirectional"))
      (node (ref "IC3") (pin "6") (pinfunction "SW_6") (pintype "bidirectional"))
      (node (ref "L2") (pin "2") (pinfunction "2_2") (pintype "bidirectional"))
    )
    (net (code "15") (name "Net-(D8-K)") (class "Default")
      (node (ref "D8") (pin "1") (pinfunction "K_1") (pintype "bidirectional"))
      (node (ref "D9") (pin "2") (pinfunction "A_2") (pintype "bidirectional"))
    )
    (net (code "16") (name "Net-(D9-K)") (class "Default")
      (node (ref "C32") (pin "2") (pinfunction "2_2") (pintype "passive"))
      (node (ref "D9") (pin "1") (pinfunction "K_1") (pintype "bidirectional"))
      (node (ref "PS1") (pin "3") (pinfunction "_+VIN_3") (pintype "bidirectional"))
    )
    (net (code "17") (name "Net-(D10-C)") (class "Default")
      (node (ref "C3") (pin "1") (pinfunction "1_1") (pintype "passive"))
      (node (ref "D10") (pin "1") (pinfunction "C_1") (pintype "passive"))
      (node (ref "R37") (pin "1") (pinfunction "1_1") (pintype "passive"))
    )
    (net (code "18") (name "Net-(D11-C)") (class "Default")
      (node (ref "C36") (pin "1") (pinfunction "1_1") (pintype "passive"))
      (node (ref "D11") (pin "1") (pinfunction "C_1") (pintype "passive"))
      (node (ref "R38") (pin "1") (pinfunction "1_1") (pintype "passive"))
    )
    (net (code "19") (name "Net-(HVLED-PadA)") (class "Default")
      (node (ref "HVLED") (pin "A") (pinfunction "A_A") (pintype "passive"))
      (node (ref "R30") (pin "1") (pinfunction "1_1") (pintype "passive"))
    )
    (net (code "20") (name "Net-(IC1-ENA)") (class "Default")
      (node (ref "IC1") (pin "1") (pinfunction "ENA_1") (pintype "bidirectional"))
      (node (ref "IC1") (pin "8") (pinfunction "ENB_8") (pintype "bidirectional"))
      (node (ref "R4") (pin "1") (pinfunction "1_1") (pintype "passive"))
    )
    (net (code "21") (name "Net-(IC1-INA)") (class "Default")
      (node (ref "IC1") (pin "2") (pinfunction "INA_2") (pintype "bidirectional"))
      (node (ref "IC2") (pin "7") (pinfunction "OUTA_7") (pintype "bidirectional"))
    )
    (net (code "22") (name "Net-(IC1-INB)") (class "Default")
      (node (ref "IC1") (pin "4") (pinfunction "INB_4") (pintype "bidirectional"))
      (node (ref "IC2") (pin "6") (pinfunction "OUTB_6") (pintype "bidirectional"))
    )
    (net (code "23") (name "Net-(IC1-OUT1)") (class "Default")
      (node (ref "IC1") (pin "7") (pinfunction "OUT1_7") (pintype "bidirectional"))
      (node (ref "R2") (pin "1") (pinfunction "1_1") (pintype "passive"))
      (node (ref "R3") (pin "1") (pinfunction "1_1") (pintype "passive"))
    )
    (net (code "24") (name "Net-(IC1-OUT2)") (class "Default")
      (node (ref "IC1") (pin "5") (pinfunction "OUT2_5") (pintype "bidirectional"))
      (node (ref "R7") (pin "1") (pinfunction "1_1") (pintype "passive"))
      (node (ref "R8") (pin "1") (pinfunction "1_1") (pintype "passive"))
    )
    (net (code "25") (name "Net-(IC2-CS)") (class "Default")
      (node (ref "C16") (pin "1") (pinfunction "1_1") (pintype "passive"))
      (node (ref "IC2") (pin "3") (pinfunction "CS_3") (pintype "bidirectional"))
      (node (ref "R11") (pin "1") (pinfunction "1_1") (pintype "passive"))
    )
    (net (code "26") (name "Net-(IC2-ISET)") (class "Default")
      (node (ref "IC2") (pin "2") (pinfunction "ISET_2") (pintype "bidirectional"))
      (node (ref "R13") (pin "1") (pinfunction "1_1") (pintype "passive"))
    )
    (net (code "27") (name "Net-(IC2-RT)") (class "Default")
      (node (ref "IC2") (pin "4") (pinfunction "RT_4") (pintype "bidirectional"))
      (node (ref "R14") (pin "1") (pinfunction "1_1") (pintype "passive"))
    )
    (net (code "28") (name "Net-(IC3-BS)") (class "Default")
      (node (ref "C20") (pin "1") (pinfunction "1_1") (pintype "passive"))
      (node (ref "IC3") (pin "1") (pinfunction "BS_1") (pintype "bidirectional"))
    )
    (net (code "29") (name "Net-(IC3-EN)") (class "Default")
      (node (ref "IC3") (pin "4") (pinfunction "EN_4") (pintype "bidirectional"))
      (node (ref "R20") (pin "2") (pinfunction "2_2") (pintype "passive"))
    )
    (net (code "30") (name "Net-(IC3-FB)") (class "Default")
      (node (ref "C19") (pin "2") (pinfunction "2_2") (pintype "passive"))
      (node (ref "IC3") (pin "3") (pinfunction "FB_3") (pintype "bidirectional"))
      (node (ref "R18") (pin "2") (pinfunction "2_2") (pintype "passive"))
      (node (ref "R19") (pin "1") (pinfunction "1_1") (pintype "passive"))
    )
    (net (code "31") (name "Net-(IC4-BS)") (class "Default")
      (node (ref "C27") (pin "2") (pinfunction "2_2") (pintype "passive"))
      (node (ref "IC4") (pin "1") (pinfunction "BS_1") (pintype "bidirectional"))
    )
    (net (code "32") (name "Net-(IC4-EN)") (class "Default")
      (node (ref "IC4") (pin "4") (pinfunction "EN_4") (pintype "bidirectional"))
      (node (ref "R33") (pin "2") (pinfunction "2_2") (pintype "passive"))
    )
    (net (code "33") (name "Net-(IC4-FB)") (class "Default")
      (node (ref "C25") (pin "2") (pinfunction "2_2") (pintype "passive"))
      (node (ref "IC4") (pin "3") (pinfunction "FB_3") (pintype "bidirectional"))
      (node (ref "R31") (pin "1") (pinfunction "1_1") (pintype "passive"))
      (node (ref "R32") (pin "1") (pinfunction "1_1") (pintype "passive"))
    )
    (net (code "34") (name "Net-(IC5-CATHODE)") (class "Default")
      (node (ref "C18") (pin "2") (pinfunction "2_2") (pintype "passive"))
      (node (ref "IC5") (pin "1") (pinfunction "CATHODE_1") (pintype "bidirectional"))
      (node (ref "OPT1") (pin "2") (pinfunction "K_2") (pintype "bidirectional"))
      (node (ref "R15") (pin "1") (pinfunction "1_1") (pintype "passive"))
    )
    (net (code "35") (name "Net-(IC5-REF)") (class "Default")
      (node (ref "C17") (pin "1") (pinfunction "1_1") (pintype "passive"))
      (node (ref "C18") (pin "1") (pinfunction "1_1") (pintype "passive"))
      (node (ref "IC5") (pin "2") (pinfunction "REF_2") (pintype "bidirectional"))
      (node (ref "J2") (pin "1") (pinfunction "1_1") (pintype "passive"))
      (node (ref "R22") (pin "2") (pinfunction "2_2") (pintype "passive"))
      (node (ref "R23") (pin "2") (pinfunction "2_2") (pintype "passive"))
    )
    (net (code "36") (name "Net-(OPT1-A)") (class "Default")
      (node (ref "OPT1") (pin "1") (pinfunction "A_1") (pintype "bidirectional"))
      (node (ref "R35") (pin "2") (pinfunction "2_2") (pintype "passive"))
    )
    (net (code "37") (name "Net-(Q1-G)") (class "Default")
      (node (ref "GATE1_TP") (pin "TP") (pinfunction "TP_TP") (pintype "input"))
      (node (ref "Q1") (pin "1") (pinfunction "G_1") (pintype "bidirectional"))
      (node (ref "R2") (pin "2") (pinfunction "2_2") (pintype "passive"))
      (node (ref "R3") (pin "2") (pinfunction "2_2") (pintype "passive"))
    )
    (net (code "38") (name "Net-(Q2-G)") (class "Default")
      (node (ref "GATE2_TP") (pin "TP") (pinfunction "TP_TP") (pintype "input"))
      (node (ref "Q2") (pin "1") (pinfunction "G_1") (pintype "bidirectional"))
      (node (ref "R7") (pin "2") (pinfunction "2_2") (pintype "passive"))
      (node (ref "R8") (pin "2") (pinfunction "2_2") (pintype "passive"))
    )
    (net (code "39") (name "Net-(R21-Pad2)") (class "Default")
      (node (ref "R21") (pin "2") (pinfunction "2_2") (pintype "passive"))
      (node (ref "R22") (pin "1") (pinfunction "1_1") (pintype "passive"))
    )
    (net (code "40") (name "Net-(R23-Pad1)") (class "Default")
      (node (ref "R23") (pin "1") (pinfunction "1_1") (pintype "passive"))
      (node (ref "R24") (pin "2") (pinfunction "2_2") (pintype "passive"))
    )
    (net (code "41") (name "Net-(R24-Pad1)") (class "Default")
      (node (ref "R24") (pin "1") (pinfunction "1_1") (pintype "passive"))
      (node (ref "R25") (pin "2") (pinfunction "2_2") (pintype "passive"))
    )
    (net (code "42") (name "Net-(R26-Pad1)") (class "Default")
      (node (ref "R26") (pin "1") (pinfunction "1_1") (pintype "passive"))
      (node (ref "R27") (pin "2") (pinfunction "2_2") (pintype "passive"))
    )
    (net (code "43") (name "Net-(R27-Pad1)") (class "Default")
      (node (ref "R27") (pin "1") (pinfunction "1_1") (pintype "passive"))
      (node (ref "R28") (pin "2") (pinfunction "2_2") (pintype "passive"))
    )
    (net (code "44") (name "Net-(R28-Pad1)") (class "Default")
      (node (ref "R28") (pin "1") (pinfunction "1_1") (pintype "passive"))
      (node (ref "R29") (pin "2") (pinfunction "2_2") (pintype "passive"))
    )
    (net (code "45") (name "Net-(R29-Pad1)") (class "Default")
      (node (ref "R29") (pin "1") (pinfunction "1_1") (pintype "passive"))
      (node (ref "R30") (pin "2") (pinfunction "2_2") (pintype "passive"))
    )
    (net (code "46") (name "Net-(VR1-ADJ)") (class "Default")
      (node (ref "R10") (pin "1") (pinfunction "1_1") (pintype "passive"))
      (node (ref "R9") (pin "2") (pinfunction "2_2") (pintype "passive"))
      (node (ref "VR1") (pin "1") (pinfunction "ADJ_1") (pintype "input"))
    )
    (net (code "47") (name "OPTO-EMITT") (class "Default")
      (node (ref "IC2") (pin "1") (pinfunction "CTRL_1") (pintype "bidirectional"))
      (node (ref "OPT1") (pin "4") (pinfunction "C_4") (pintype "bidirectional"))
      (node (ref "R12") (pin "2") (pinfunction "2_2") (pintype "passive"))
    )
    (net (code "48") (name "PRE") (class "Default")
      (node (ref "C25") (pin "1") (pinfunction "1_1") (pintype "passive"))
      (node (ref "C28") (pin "2") (pinfunction "2_2") (pintype "passive"))
      (node (ref "C29") (pin "2") (pinfunction "2_2") (pintype "passive"))
      (node (ref "C30") (pin "2") (pinfunction "2_2") (pintype "passive"))
      (node (ref "L3") (pin "2") (pinfunction "2_2") (pintype "bidirectional"))
      (node (ref "MAINBUCK_TP") (pin "TP") (pinfunction "TP_TP") (pintype "input"))
      (node (ref "R32") (pin "2") (pinfunction "2_2") (pintype "passive"))
      (node (ref "VR1") (pin "3") (pinfunction "IN_3") (pintype "input"))
    )
    (net (code "49") (name "PWRGND") (class "Default")
      (node (ref "C21") (pin "2") (pinfunction "2_2") (pintype "passive"))
      (node (ref "C22") (pin "1") (pinfunction "1_1") (pintype "passive"))
      (node (ref "C23") (pin "1") (pinfunction "1_1") (pintype "passive"))
      (node (ref "C24") (pin "1") (pinfunction "1_1") (pintype "passive"))
      (node (ref "C33") (pin "1") (pinfunction "1_1") (pintype "passive"))
      (node (ref "C34") (pin "2") (pinfunction "2_2") (pintype "passive"))
      (node (ref "C35") (pin "1") (pinfunction "1_1") (pintype "passive"))
      (node (ref "C4") (pin "2") (pinfunction "2_2") (pintype "bidirectional"))
      (node (ref "C5") (pin "2") (pinfunction "2_2") (pintype "bidirectional"))
      (node (ref "C6") (pin "2") (pinfunction "-_2") (pintype "bidirectional"))
      (node (ref "C7") (pin "2") (pinfunction "-_2") (pintype "bidirectional"))
      (node (ref "D1") (pin "2") (pinfunction "A_2") (pintype "bidirectional"))
      (node (ref "D3") (pin "2") (pinfunction "A_2") (pintype "bidirectional"))
      (node (ref "D7") (pin "2") (pinfunction "A_2") (pintype "bidirectional"))
      (node (ref "HVLED") (pin "C") (pinfunction "C_C") (pintype "passive"))
      (node (ref "IC3") (pin "2") (pinfunction "GND_2") (pintype "bidirectional"))
      (node (ref "IC5") (pin "3") (pinfunction "ANODE_3") (pintype "bidirectional"))
      (node (ref "J1") (pin "1") (pinfunction "1_1") (pintype "bidirectional"))
      (node (ref "J2") (pin "2") (pinfunction "2_2") (pintype "passive"))
      (node (ref "PS1") (pin "7") (pinfunction "-VOUT_7") (pintype "bidirectional"))
      (node (ref "PWRGND_TP") (pin "TP") (pinfunction "TP_TP") (pintype "input"))
      (node (ref "R19") (pin "2") (pinfunction "2_2") (pintype "passive"))
      (node (ref "R21") (pin "1") (pinfunction "1_1") (pintype "passive"))
      (node (ref "R36") (pin "1") (pinfunction "1_1") (pintype "passive"))
      (node (ref "T1") (pin "15") (pinfunction "15_15") (pintype "bidirectional"))
      (node (ref "T1.1") (pin "4") (pinfunction "4_4") (pintype "bidirectional"))
      (node (ref "VR2") (pin "1") (pinfunction "GND_1") (pintype "bidirectional"))
      (node (ref "Z3") (pin "2") (pinfunction "A_2") (pintype "bidirectional"))
    )
    (net (code "50") (name "RECT") (class "Default")
      (node (ref "D2") (pin "1") (pinfunction "K_1_1") (pintype "bidirectional"))
      (node (ref "D2") (pin "3") (pinfunction "K_2_3") (pintype "bidirectional"))
      (node (ref "D4") (pin "1") (pinfunction "K_1_1") (pintype "bidirectional"))
      (node (ref "D4") (pin "3") (pinfunction "K_2_3") (pintype "bidirectional"))
      (node (ref "L1") (pin "1") (pinfunction "1_1") (pintype "bidirectional"))
    )
    (net (code "51") (name "REG") (class "Default")
      (node (ref "13.75V") (pin "A") (pinfunction "A_A") (pintype "passive"))
      (node (ref "13.75V_TP") (pin "TP") (pinfunction "TP_TP") (pintype "input"))
      (node (ref "C10") (pin "1") (pinfunction "1_1") (pintype "passive"))
      (node (ref "C14") (pin "1") (pinfunction "1_1") (pintype "passive"))
      (node (ref "C15") (pin "1") (pinfunction "1_1") (pintype "passive"))
      (node (ref "C31") (pin "2") (pinfunction "2_2") (pintype "passive"))
      (node (ref "C9") (pin "1") (pinfunction "1_1") (pintype "passive"))
      (node (ref "D8") (pin "2") (pinfunction "A_2") (pintype "bidirectional"))
      (node (ref "IC1") (pin "6") (pinfunction "VDD_6") (pintype "bidirectional"))
      (node (ref "IC2") (pin "8") (pinfunction "VDD_8") (pintype "bidirectional"))
      (node (ref "R10") (pin "2") (pinfunction "2_2") (pintype "passive"))
      (node (ref "R12") (pin "1") (pinfunction "1_1") (pintype "passive"))
      (node (ref "R4") (pin "2") (pinfunction "2_2") (pintype "passive"))
      (node (ref "VR1") (pin "4") (pinfunction "OUT_4") (pintype "passive"))
    )
    (net (code "52") (name "REG5V") (class "Default")
      (node (ref "5VLED") (pin "A") (pinfunction "A_A") (pintype "passive"))
      (node (ref "AUX5V_TP") (pin "TP") (pinfunction "TP_TP") (pintype "input"))
      (node (ref "C33") (pin "2") (pinfunction "2_2") (pintype "passive"))
      (node (ref "C35") (pin "2") (pinfunction "2_2") (pintype "passive"))
      (node (ref "PS1") (pin "8") (pinfunction "+VOUT_8") (pintype "bidirectional"))
      (node (ref "R35") (pin "1") (pinfunction "1_1") (pintype "passive"))
      (node (ref "VR2") (pin "2") (pinfunction "VOUT_2") (pintype "bidirectional"))
    )
    (net (code "53") (name "TRANS1") (class "Default")
      (node (ref "D1") (pin "1") (pinfunction "K_1_1") (pintype "bidirectional"))
      (node (ref "D1") (pin "3") (pinfunction "K_2_3") (pintype "bidirectional"))
      (node (ref "D2") (pin "2") (pinfunction "A_2") (pintype "bidirectional"))
      (node (ref "T1") (pin "11") (pinfunction "11_11") (pintype "bidirectional"))
      (node (ref "T1.1") (pin "8") (pinfunction "8_8") (pintype "bidirectional"))
    )
    (net (code "54") (name "TRANS2") (class "Default")
      (node (ref "D3") (pin "1") (pinfunction "K_1_1") (pintype "bidirectional"))
      (node (ref "D3") (pin "3") (pinfunction "K_2_3") (pintype "bidirectional"))
      (node (ref "D4") (pin "2") (pinfunction "A_2") (pintype "bidirectional"))
      (node (ref "T1") (pin "9") (pinfunction "9_9") (pintype "bidirectional"))
      (node (ref "T1.1") (pin "14") (pinfunction "14_14") (pintype "bidirectional"))
    )
    (net (code "55") (name "VCC28V") (class "Default")
      (node (ref "C1") (pin "1") (pinfunction "+_1") (pintype "bidirectional"))
      (node (ref "C11") (pin "2") (pinfunction "2_2") (pintype "passive"))
      (node (ref "C12") (pin "1") (pinfunction "+_1") (pintype "bidirectional"))
      (node (ref "C13") (pin "1") (pinfunction "+_1") (pintype "bidirectional"))
      (node (ref "C2") (pin "1") (pinfunction "+_1") (pintype "bidirectional"))
      (node (ref "C26") (pin "1") (pinfunction "1_1") (pintype "passive"))
      (node (ref "C3") (pin "2") (pinfunction "2_2") (pintype "passive"))
      (node (ref "C36") (pin "2") (pinfunction "2_2") (pintype "passive"))
      (node (ref "C8") (pin "1") (pinfunction "1_1") (pintype "passive"))
      (node (ref "IC4") (pin "5") (pinfunction "IN_5") (pintype "bidirectional"))
      (node (ref "INPUT") (pin "1") (pinfunction "1_1") (pintype "bidirectional"))
      (node (ref "R33") (pin "1") (pinfunction "1_1") (pintype "passive"))
      (node (ref "R37") (pin "2") (pinfunction "2_2") (pintype "passive"))
      (node (ref "R38") (pin "2") (pinfunction "2_2") (pintype "passive"))
      (node (ref "T1") (pin "4") (pinfunction "4_4") (pintype "bidirectional"))
      (node (ref "T1") (pin "5") (pinfunction "5_5") (pintype "bidirectional"))
      (node (ref "T1.1") (pin "7") (pinfunction "7_7") (pintype "bidirectional"))
    )
    (net (code "56") (name "unconnected-(PS1-NA-Pad14)") (class "Default")
      (node (ref "PS1") (pin "14") (pinfunction "NA_14") (pintype "bidirectional"))
    )
    (net (code "57") (name "unconnected-(T1-Pad10)") (class "Default")
      (node (ref "T1") (pin "10") (pinfunction "10_10") (pintype "bidirectional"))
    )
    (net (code "58") (name "unconnected-(T1-Pad12)") (class "Default")
      (node (ref "T1") (pin "12") (pinfunction "12_12") (pintype "bidirectional"))
    )
    (net (code "59") (name "unconnected-(T1-Pad13)") (class "Default")
      (node (ref "T1") (pin "13") (pinfunction "13_13") (pintype "bidirectional"))
    )
    (net (code "60") (name "unconnected-(T1-Pad14)") (class "Default")
      (node (ref "T1") (pin "14") (pinfunction "14_14") (pintype "bidirectional"))
    )
    (net (code "61") (name "unconnected-(T1.1-Pad6)") (class "Default")
      (node (ref "T1.1") (pin "6") (pinfunction "6_6") (pintype "bidirectional"))
    )
    (net (code "62") (name "unconnected-(T1.1-Pad10)") (class "Default")
      (node (ref "T1.1") (pin "10") (pinfunction "10_10") (pintype "bidirectional"))
    )
    (net (code "63") (name "unconnected-(T1.1-Pad12)") (class "Default")
      (node (ref "T1.1") (pin "12") (pinfunction "12_12") (pintype "bidirectional"))
    )
  )
)
